# 8_Relay_Buzz_SCT013.net
KiCad netlist of a schematic drawn in EAGLE
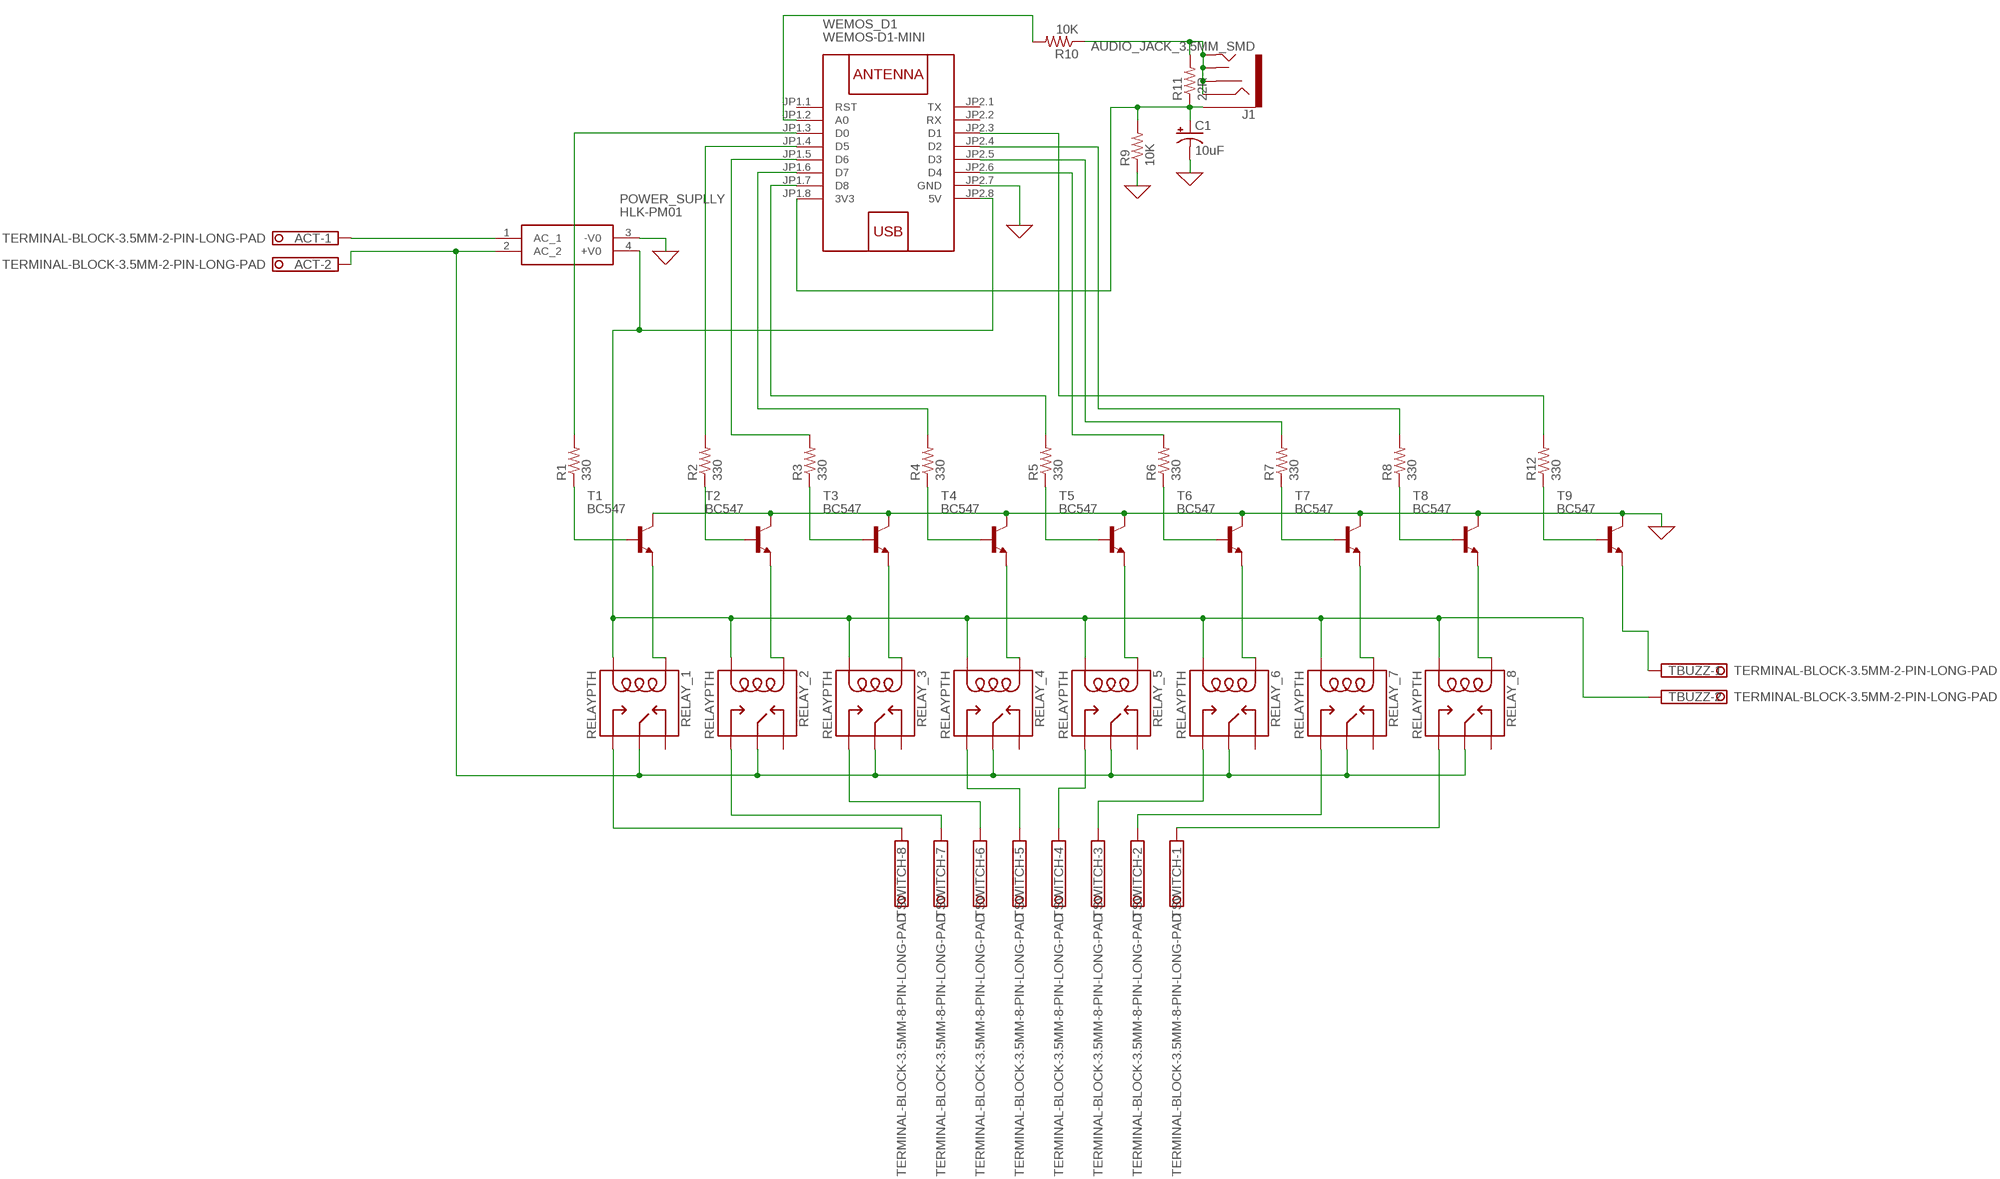
[diagram p0: schematic, sheet 1]

(export (version "E")
  (design (tool "Eeschema 10.0.6"))
  (components
    (comp (ref "ACT")
      (value "TERMINAL-BLOCK-3.5MM-2-PIN-LONG-PAD")
      (footprint "eagle-import:TERMINAL-BLOCK-2-PIN-3.5MM-LONG-PAD")
      (libsource (lib "eagle-import") (part "TERMINAL-BLOCK-3.5MM-2-PIN-LONG-PAD"))
    )
    (comp (ref "C1")
      (value "10uF")
      (footprint "eagle-import:E3,5-8")
      (libsource (lib "eagle-import") (part "CPOL-USE3.5-8"))
    )
    (comp (ref "J1")
      (value "AUDIO_JACK_3.5MM_SMD")
      (footprint "eagle-import:AUDIO-JACK-3.5MM-SMD")
      (libsource (lib "eagle-import") (part "AUDIO_JACK_3.5MM_SMD"))
    )
    (comp (ref "POWER_SUPLLY")
      (value "HLK-PM01")
      (footprint "eagle-import:HLKPM01")
      (fields (field (name "MF") "Hi-link") (field (name "MP") "hlk-pm01"))
      (libsource (lib "eagle-import") (part "HLK-PM01"))
    )
    (comp (ref "R1")
      (value "330")
      (footprint "eagle-import:0207_5V")
      (libsource (lib "eagle-import") (part "R-US_0207/5V"))
    )
    (comp (ref "R2")
      (value "330")
      (footprint "eagle-import:0207_5V")
      (libsource (lib "eagle-import") (part "R-US_0207/5V"))
    )
    (comp (ref "R3")
      (value "330")
      (footprint "eagle-import:0207_5V")
      (libsource (lib "eagle-import") (part "R-US_0207/5V"))
    )
    (comp (ref "R4")
      (value "330")
      (footprint "eagle-import:0207_5V")
      (libsource (lib "eagle-import") (part "R-US_0207/5V"))
    )
    (comp (ref "R5")
      (value "330")
      (footprint "eagle-import:0207_5V")
      (libsource (lib "eagle-import") (part "R-US_0207/5V"))
    )
    (comp (ref "R6")
      (value "330")
      (footprint "eagle-import:0207_5V")
      (libsource (lib "eagle-import") (part "R-US_0207/5V"))
    )
    (comp (ref "R7")
      (value "330")
      (footprint "eagle-import:0207_5V")
      (libsource (lib "eagle-import") (part "R-US_0207/5V"))
    )
    (comp (ref "R8")
      (value "330")
      (footprint "eagle-import:0207_5V")
      (libsource (lib "eagle-import") (part "R-US_0207/5V"))
    )
    (comp (ref "R9")
      (value "10K")
      (footprint "eagle-import:0207_5V")
      (libsource (lib "eagle-import") (part "R-US_0207/5V"))
    )
    (comp (ref "R10")
      (value "10K")
      (footprint "eagle-import:0207_5V")
      (libsource (lib "eagle-import") (part "R-US_0207/5V"))
    )
    (comp (ref "R11")
      (value "22R")
      (footprint "eagle-import:0207_5V")
      (libsource (lib "eagle-import") (part "R-US_0207/5V"))
    )
    (comp (ref "R12")
      (value "330")
      (footprint "eagle-import:0207_5V")
      (libsource (lib "eagle-import") (part "R-US_0207/5V"))
    )
    (comp (ref "RELAY_1")
      (value "RELAYPTH")
      (footprint "eagle-import:SRD-05VDC-SL-C")
      (libsource (lib "eagle-import") (part "RELAYPTH"))
    )
    (comp (ref "RELAY_2")
      (value "RELAYPTH")
      (footprint "eagle-import:SRD-05VDC-SL-C")
      (libsource (lib "eagle-import") (part "RELAYPTH"))
    )
    (comp (ref "RELAY_3")
      (value "RELAYPTH")
      (footprint "eagle-import:SRD-05VDC-SL-C")
      (libsource (lib "eagle-import") (part "RELAYPTH"))
    )
    (comp (ref "RELAY_4")
      (value "RELAYPTH")
      (footprint "eagle-import:SRD-05VDC-SL-C")
      (libsource (lib "eagle-import") (part "RELAYPTH"))
    )
    (comp (ref "RELAY_5")
      (value "RELAYPTH")
      (footprint "eagle-import:SRD-05VDC-SL-C")
      (libsource (lib "eagle-import") (part "RELAYPTH"))
    )
    (comp (ref "RELAY_6")
      (value "RELAYPTH")
      (footprint "eagle-import:SRD-05VDC-SL-C")
      (libsource (lib "eagle-import") (part "RELAYPTH"))
    )
    (comp (ref "RELAY_7")
      (value "RELAYPTH")
      (footprint "eagle-import:SRD-05VDC-SL-C")
      (libsource (lib "eagle-import") (part "RELAYPTH"))
    )
    (comp (ref "RELAY_8")
      (value "RELAYPTH")
      (footprint "eagle-import:SRD-05VDC-SL-C")
      (libsource (lib "eagle-import") (part "RELAYPTH"))
    )
    (comp (ref "T1")
      (value "BC547")
      (footprint "eagle-import:TO92")
      (libsource (lib "eagle-import") (part "BC547"))
    )
    (comp (ref "T2")
      (value "BC547")
      (footprint "eagle-import:TO92")
      (libsource (lib "eagle-import") (part "BC547"))
    )
    (comp (ref "T3")
      (value "BC547")
      (footprint "eagle-import:TO92")
      (libsource (lib "eagle-import") (part "BC547"))
    )
    (comp (ref "T4")
      (value "BC547")
      (footprint "eagle-import:TO92")
      (libsource (lib "eagle-import") (part "BC547"))
    )
    (comp (ref "T5")
      (value "BC547")
      (footprint "eagle-import:TO92")
      (libsource (lib "eagle-import") (part "BC547"))
    )
    (comp (ref "T6")
      (value "BC547")
      (footprint "eagle-import:TO92")
      (libsource (lib "eagle-import") (part "BC547"))
    )
    (comp (ref "T7")
      (value "BC547")
      (footprint "eagle-import:TO92")
      (libsource (lib "eagle-import") (part "BC547"))
    )
    (comp (ref "T8")
      (value "BC547")
      (footprint "eagle-import:TO92")
      (libsource (lib "eagle-import") (part "BC547"))
    )
    (comp (ref "T9")
      (value "BC547")
      (footprint "eagle-import:TO92")
      (libsource (lib "eagle-import") (part "BC547"))
    )
    (comp (ref "TBUZZ")
      (value "TERMINAL-BLOCK-3.5MM-2-PIN-LONG-PAD")
      (footprint "eagle-import:TERMINAL-BLOCK-2-PIN-3.5MM-LONG-PAD")
      (libsource (lib "eagle-import") (part "TERMINAL-BLOCK-3.5MM-2-PIN-LONG-PAD"))
    )
    (comp (ref "TSWITCH")
      (value "TERMINAL-BLOCK-3.5MM-8-PIN-LONG-PAD")
      (footprint "eagle-import:TERMINAL-BLOCK-8-PIN-3.5MM-LONG-PAD")
      (libsource (lib "eagle-import") (part "TERMINAL-BLOCK-3.5MM-8-PIN-LONG-PAD"))
    )
    (comp (ref "WEMOS_D1")
      (value "WEMOS-D1-MINI")
      (footprint "eagle-import:WEMOS-D1-MINI")
      (libsource (lib "eagle-import") (part "WEMOS-D1-MINI"))
    )
  )
  (nets
    (net (code "1") (name "GND") (class "Default")
      (node (ref "C1") (pin "-") (pinfunction "-_-") (pintype "passive"))
      (node (ref "POWER_SUPLLY") (pin "3") (pinfunction "-V0_3") (pintype "bidirectional"))
      (node (ref "R9") (pin "1") (pinfunction "1_1") (pintype "passive"))
      (node (ref "T1") (pin "3") (pinfunction "C_3") (pintype "passive"))
      (node (ref "T2") (pin "3") (pinfunction "C_3") (pintype "passive"))
      (node (ref "T3") (pin "3") (pinfunction "C_3") (pintype "passive"))
      (node (ref "T4") (pin "3") (pinfunction "C_3") (pintype "passive"))
      (node (ref "T5") (pin "3") (pinfunction "C_3") (pintype "passive"))
      (node (ref "T6") (pin "3") (pinfunction "C_3") (pintype "passive"))
      (node (ref "T7") (pin "3") (pinfunction "C_3") (pintype "passive"))
      (node (ref "T8") (pin "3") (pinfunction "C_3") (pintype "passive"))
      (node (ref "T9") (pin "3") (pinfunction "C_3") (pintype "passive"))
      (node (ref "WEMOS_D1") (pin "JP2.7") (pinfunction "GND_JP2.7") (pintype "power_in"))
    )
    (net (code "2") (name "Net-(ACTA-K)") (class "Default")
      (node (ref "ACT") (pin "1") (pinfunction "K_1") (pintype "passive"))
      (node (ref "POWER_SUPLLY") (pin "1") (pinfunction "AC_1_1") (pintype "bidirectional"))
    )
    (net (code "3") (name "Net-(ACTB-K)") (class "Default")
      (node (ref "ACT") (pin "2") (pinfunction "K_2") (pintype "passive"))
      (node (ref "POWER_SUPLLY") (pin "2") (pinfunction "AC_2_2") (pintype "bidirectional"))
      (node (ref "RELAY_1") (pin "SWCOMMON") (pinfunction "SWCOMMON_SWCOMMON") (pintype "bidirectional"))
      (node (ref "RELAY_2") (pin "SWCOMMON") (pinfunction "SWCOMMON_SWCOMMON") (pintype "bidirectional"))
      (node (ref "RELAY_3") (pin "SWCOMMON") (pinfunction "SWCOMMON_SWCOMMON") (pintype "bidirectional"))
      (node (ref "RELAY_4") (pin "SWCOMMON") (pinfunction "SWCOMMON_SWCOMMON") (pintype "bidirectional"))
      (node (ref "RELAY_5") (pin "SWCOMMON") (pinfunction "SWCOMMON_SWCOMMON") (pintype "bidirectional"))
      (node (ref "RELAY_6") (pin "SWCOMMON") (pinfunction "SWCOMMON_SWCOMMON") (pintype "bidirectional"))
      (node (ref "RELAY_7") (pin "SWCOMMON") (pinfunction "SWCOMMON_SWCOMMON") (pintype "bidirectional"))
      (node (ref "RELAY_8") (pin "SWCOMMON") (pinfunction "SWCOMMON_SWCOMMON") (pintype "bidirectional"))
    )
    (net (code "4") (name "Net-(J1-PadRING)") (class "Default")
      (node (ref "J1") (pin "RING") (pinfunction "RING_RING") (pintype "bidirectional"))
      (node (ref "J1") (pin "RSH") (pinfunction "RSH_RSH") (pintype "bidirectional"))
      (node (ref "J1") (pin "TIP") (pinfunction "TIP_TIP") (pintype "bidirectional"))
      (node (ref "J1") (pin "TSH") (pinfunction "TSH_TSH") (pintype "bidirectional"))
      (node (ref "R10") (pin "1") (pinfunction "1_1") (pintype "passive"))
      (node (ref "R11") (pin "2") (pinfunction "2_2") (pintype "passive"))
    )
    (net (code "5") (name "Net-(POWER_SUPLLY-+V0)") (class "Default")
      (node (ref "POWER_SUPLLY") (pin "4") (pinfunction "+V0_4") (pintype "bidirectional"))
      (node (ref "RELAY_1") (pin "COIL0") (pinfunction "COIL0_COIL0") (pintype "bidirectional"))
      (node (ref "RELAY_2") (pin "COIL0") (pinfunction "COIL0_COIL0") (pintype "bidirectional"))
      (node (ref "RELAY_3") (pin "COIL0") (pinfunction "COIL0_COIL0") (pintype "bidirectional"))
      (node (ref "RELAY_4") (pin "COIL0") (pinfunction "COIL0_COIL0") (pintype "bidirectional"))
      (node (ref "RELAY_5") (pin "COIL0") (pinfunction "COIL0_COIL0") (pintype "bidirectional"))
      (node (ref "RELAY_6") (pin "COIL0") (pinfunction "COIL0_COIL0") (pintype "bidirectional"))
      (node (ref "RELAY_7") (pin "COIL0") (pinfunction "COIL0_COIL0") (pintype "bidirectional"))
      (node (ref "RELAY_8") (pin "COIL0") (pinfunction "COIL0_COIL0") (pintype "bidirectional"))
      (node (ref "TBUZZ") (pin "2") (pinfunction "K_2") (pintype "passive"))
      (node (ref "WEMOS_D1") (pin "JP2.8") (pinfunction "5V_JP2.8") (pintype "power_in"))
    )
    (net (code "6") (name "Net-(T1-B)") (class "Default")
      (node (ref "R1") (pin "1") (pinfunction "1_1") (pintype "passive"))
      (node (ref "T1") (pin "2") (pinfunction "B_2") (pintype "passive"))
    )
    (net (code "7") (name "Net-(T1-E)") (class "Default")
      (node (ref "RELAY_1") (pin "COIL1") (pinfunction "COIL1_COIL1") (pintype "bidirectional"))
      (node (ref "T1") (pin "1") (pinfunction "E_1") (pintype "passive"))
    )
    (net (code "8") (name "Net-(T2-B)") (class "Default")
      (node (ref "R2") (pin "1") (pinfunction "1_1") (pintype "passive"))
      (node (ref "T2") (pin "2") (pinfunction "B_2") (pintype "passive"))
    )
    (net (code "9") (name "Net-(T2-E)") (class "Default")
      (node (ref "RELAY_2") (pin "COIL1") (pinfunction "COIL1_COIL1") (pintype "bidirectional"))
      (node (ref "T2") (pin "1") (pinfunction "E_1") (pintype "passive"))
    )
    (net (code "10") (name "Net-(T3-B)") (class "Default")
      (node (ref "R3") (pin "1") (pinfunction "1_1") (pintype "passive"))
      (node (ref "T3") (pin "2") (pinfunction "B_2") (pintype "passive"))
    )
    (net (code "11") (name "Net-(T3-E)") (class "Default")
      (node (ref "RELAY_3") (pin "COIL1") (pinfunction "COIL1_COIL1") (pintype "bidirectional"))
      (node (ref "T3") (pin "1") (pinfunction "E_1") (pintype "passive"))
    )
    (net (code "12") (name "Net-(T4-B)") (class "Default")
      (node (ref "R4") (pin "1") (pinfunction "1_1") (pintype "passive"))
      (node (ref "T4") (pin "2") (pinfunction "B_2") (pintype "passive"))
    )
    (net (code "13") (name "Net-(T4-E)") (class "Default")
      (node (ref "RELAY_4") (pin "COIL1") (pinfunction "COIL1_COIL1") (pintype "bidirectional"))
      (node (ref "T4") (pin "1") (pinfunction "E_1") (pintype "passive"))
    )
    (net (code "14") (name "Net-(T5-B)") (class "Default")
      (node (ref "R5") (pin "1") (pinfunction "1_1") (pintype "passive"))
      (node (ref "T5") (pin "2") (pinfunction "B_2") (pintype "passive"))
    )
    (net (code "15") (name "Net-(T5-E)") (class "Default")
      (node (ref "RELAY_5") (pin "COIL1") (pinfunction "COIL1_COIL1") (pintype "bidirectional"))
      (node (ref "T5") (pin "1") (pinfunction "E_1") (pintype "passive"))
    )
    (net (code "16") (name "Net-(T6-B)") (class "Default")
      (node (ref "R6") (pin "1") (pinfunction "1_1") (pintype "passive"))
      (node (ref "T6") (pin "2") (pinfunction "B_2") (pintype "passive"))
    )
    (net (code "17") (name "Net-(T6-E)") (class "Default")
      (node (ref "RELAY_6") (pin "COIL1") (pinfunction "COIL1_COIL1") (pintype "bidirectional"))
      (node (ref "T6") (pin "1") (pinfunction "E_1") (pintype "passive"))
    )
    (net (code "18") (name "Net-(T7-B)") (class "Default")
      (node (ref "R7") (pin "1") (pinfunction "1_1") (pintype "passive"))
      (node (ref "T7") (pin "2") (pinfunction "B_2") (pintype "passive"))
    )
    (net (code "19") (name "Net-(T7-E)") (class "Default")
      (node (ref "RELAY_7") (pin "COIL1") (pinfunction "COIL1_COIL1") (pintype "bidirectional"))
      (node (ref "T7") (pin "1") (pinfunction "E_1") (pintype "passive"))
    )
    (net (code "20") (name "Net-(T8-B)") (class "Default")
      (node (ref "R8") (pin "1") (pinfunction "1_1") (pintype "passive"))
      (node (ref "T8") (pin "2") (pinfunction "B_2") (pintype "passive"))
    )
    (net (code "21") (name "Net-(T8-E)") (class "Default")
      (node (ref "RELAY_8") (pin "COIL1") (pinfunction "COIL1_COIL1") (pintype "bidirectional"))
      (node (ref "T8") (pin "1") (pinfunction "E_1") (pintype "passive"))
    )
    (net (code "22") (name "Net-(T9-B)") (class "Default")
      (node (ref "R12") (pin "1") (pinfunction "1_1") (pintype "passive"))
      (node (ref "T9") (pin "2") (pinfunction "B_2") (pintype "passive"))
    )
    (net (code "23") (name "Net-(T9-E)") (class "Default")
      (node (ref "T9") (pin "1") (pinfunction "E_1") (pintype "passive"))
      (node (ref "TBUZZ") (pin "1") (pinfunction "K_1") (pintype "passive"))
    )
    (net (code "24") (name "Net-(TSWITCHA-K)") (class "Default")
      (node (ref "RELAY_8") (pin "SWOPEN") (pinfunction "SWOPEN_SWOPEN") (pintype "bidirectional"))
      (node (ref "TSWITCH") (pin "1") (pinfunction "K_1") (pintype "passive"))
    )
    (net (code "25") (name "Net-(TSWITCHB-K)") (class "Default")
      (node (ref "RELAY_7") (pin "SWOPEN") (pinfunction "SWOPEN_SWOPEN") (pintype "bidirectional"))
      (node (ref "TSWITCH") (pin "2") (pinfunction "K_2") (pintype "passive"))
    )
    (net (code "26") (name "Net-(TSWITCHC-K)") (class "Default")
      (node (ref "RELAY_6") (pin "SWOPEN") (pinfunction "SWOPEN_SWOPEN") (pintype "bidirectional"))
      (node (ref "TSWITCH") (pin "3") (pinfunction "K_3") (pintype "passive"))
    )
    (net (code "27") (name "Net-(TSWITCHD-K)") (class "Default")
      (node (ref "RELAY_5") (pin "SWOPEN") (pinfunction "SWOPEN_SWOPEN") (pintype "bidirectional"))
      (node (ref "TSWITCH") (pin "4") (pinfunction "K_4") (pintype "passive"))
    )
    (net (code "28") (name "Net-(TSWITCHE-K)") (class "Default")
      (node (ref "RELAY_4") (pin "SWOPEN") (pinfunction "SWOPEN_SWOPEN") (pintype "bidirectional"))
      (node (ref "TSWITCH") (pin "5") (pinfunction "K_5") (pintype "passive"))
    )
    (net (code "29") (name "Net-(TSWITCHF-K)") (class "Default")
      (node (ref "RELAY_3") (pin "SWOPEN") (pinfunction "SWOPEN_SWOPEN") (pintype "bidirectional"))
      (node (ref "TSWITCH") (pin "6") (pinfunction "K_6") (pintype "passive"))
    )
    (net (code "30") (name "Net-(TSWITCHG-K)") (class "Default")
      (node (ref "RELAY_2") (pin "SWOPEN") (pinfunction "SWOPEN_SWOPEN") (pintype "bidirectional"))
      (node (ref "TSWITCH") (pin "7") (pinfunction "K_7") (pintype "passive"))
    )
    (net (code "31") (name "Net-(TSWITCHH-K)") (class "Default")
      (node (ref "RELAY_1") (pin "SWOPEN") (pinfunction "SWOPEN_SWOPEN") (pintype "bidirectional"))
      (node (ref "TSWITCH") (pin "8") (pinfunction "K_8") (pintype "passive"))
    )
    (net (code "32") (name "Net-(WEMOS_D1-3V3)") (class "Default")
      (node (ref "C1") (pin "+") (pinfunction "+_+") (pintype "passive"))
      (node (ref "J1") (pin "SLEEVE") (pinfunction "SLEEVE_SLEEVE") (pintype "bidirectional"))
      (node (ref "R11") (pin "1") (pinfunction "1_1") (pintype "passive"))
      (node (ref "R9") (pin "2") (pinfunction "2_2") (pintype "passive"))
      (node (ref "WEMOS_D1") (pin "JP1.8") (pinfunction "3V3_JP1.8") (pintype "power_in"))
    )
    (net (code "33") (name "Net-(WEMOS_D1-A0)") (class "Default")
      (node (ref "R10") (pin "2") (pinfunction "2_2") (pintype "passive"))
      (node (ref "WEMOS_D1") (pin "JP1.2") (pinfunction "A0_JP1.2") (pintype "bidirectional"))
    )
    (net (code "34") (name "Net-(WEMOS_D1-D0)") (class "Default")
      (node (ref "R1") (pin "2") (pinfunction "2_2") (pintype "passive"))
      (node (ref "WEMOS_D1") (pin "JP1.3") (pinfunction "D0_JP1.3") (pintype "bidirectional"))
    )
    (net (code "35") (name "Net-(WEMOS_D1-D1)") (class "Default")
      (node (ref "R12") (pin "2") (pinfunction "2_2") (pintype "passive"))
      (node (ref "WEMOS_D1") (pin "JP2.3") (pinfunction "D1_JP2.3") (pintype "bidirectional"))
    )
    (net (code "36") (name "Net-(WEMOS_D1-D2)") (class "Default")
      (node (ref "R8") (pin "2") (pinfunction "2_2") (pintype "passive"))
      (node (ref "WEMOS_D1") (pin "JP2.4") (pinfunction "D2_JP2.4") (pintype "bidirectional"))
    )
    (net (code "37") (name "Net-(WEMOS_D1-D3)") (class "Default")
      (node (ref "R7") (pin "2") (pinfunction "2_2") (pintype "passive"))
      (node (ref "WEMOS_D1") (pin "JP2.5") (pinfunction "D3_JP2.5") (pintype "bidirectional"))
    )
    (net (code "38") (name "Net-(WEMOS_D1-D4)") (class "Default")
      (node (ref "R6") (pin "2") (pinfunction "2_2") (pintype "passive"))
      (node (ref "WEMOS_D1") (pin "JP2.6") (pinfunction "D4_JP2.6") (pintype "bidirectional"))
    )
    (net (code "39") (name "Net-(WEMOS_D1-D5)") (class "Default")
      (node (ref "R2") (pin "2") (pinfunction "2_2") (pintype "passive"))
      (node (ref "WEMOS_D1") (pin "JP1.4") (pinfunction "D5_JP1.4") (pintype "bidirectional"))
    )
    (net (code "40") (name "Net-(WEMOS_D1-D6)") (class "Default")
      (node (ref "R3") (pin "2") (pinfunction "2_2") (pintype "passive"))
      (node (ref "WEMOS_D1") (pin "JP1.5") (pinfunction "D6_JP1.5") (pintype "bidirectional"))
    )
    (net (code "41") (name "Net-(WEMOS_D1-D7)") (class "Default")
      (node (ref "R4") (pin "2") (pinfunction "2_2") (pintype "passive"))
      (node (ref "WEMOS_D1") (pin "JP1.6") (pinfunction "D7_JP1.6") (pintype "bidirectional"))
    )
    (net (code "42") (name "Net-(WEMOS_D1-D8)") (class "Default")
      (node (ref "R5") (pin "2") (pinfunction "2_2") (pintype "passive"))
      (node (ref "WEMOS_D1") (pin "JP1.7") (pinfunction "D8_JP1.7") (pintype "bidirectional"))
    )
    (net (code "43") (name "unconnected-(RELAY_1-SWCLOSE-PadSWCLOSED)") (class "Default")
      (node (ref "RELAY_1") (pin "SWCLOSED") (pinfunction "SWCLOSE_SWCLOSED") (pintype "bidirectional"))
    )
    (net (code "44") (name "unconnected-(RELAY_2-SWCLOSE-PadSWCLOSED)") (class "Default")
      (node (ref "RELAY_2") (pin "SWCLOSED") (pinfunction "SWCLOSE_SWCLOSED") (pintype "bidirectional"))
    )
    (net (code "45") (name "unconnected-(RELAY_3-SWCLOSE-PadSWCLOSED)") (class "Default")
      (node (ref "RELAY_3") (pin "SWCLOSED") (pinfunction "SWCLOSE_SWCLOSED") (pintype "bidirectional"))
    )
    (net (code "46") (name "unconnected-(RELAY_4-SWCLOSE-PadSWCLOSED)") (class "Default")
      (node (ref "RELAY_4") (pin "SWCLOSED") (pinfunction "SWCLOSE_SWCLOSED") (pintype "bidirectional"))
    )
    (net (code "47") (name "unconnected-(RELAY_5-SWCLOSE-PadSWCLOSED)") (class "Default")
      (node (ref "RELAY_5") (pin "SWCLOSED") (pinfunction "SWCLOSE_SWCLOSED") (pintype "bidirectional"))
    )
    (net (code "48") (name "unconnected-(RELAY_6-SWCLOSE-PadSWCLOSED)") (class "Default")
      (node (ref "RELAY_6") (pin "SWCLOSED") (pinfunction "SWCLOSE_SWCLOSED") (pintype "bidirectional"))
    )
    (net (code "49") (name "unconnected-(RELAY_7-SWCLOSE-PadSWCLOSED)") (class "Default")
      (node (ref "RELAY_7") (pin "SWCLOSED") (pinfunction "SWCLOSE_SWCLOSED") (pintype "bidirectional"))
    )
    (net (code "50") (name "unconnected-(RELAY_8-SWCLOSE-PadSWCLOSED)") (class "Default")
      (node (ref "RELAY_8") (pin "SWCLOSED") (pinfunction "SWCLOSE_SWCLOSED") (pintype "bidirectional"))
    )
    (net (code "51") (name "unconnected-(WEMOS_D1-RST-PadJP1.1)") (class "Default")
      (node (ref "WEMOS_D1") (pin "JP1.1") (pinfunction "RST_JP1.1") (pintype "bidirectional"))
    )
    (net (code "52") (name "unconnected-(WEMOS_D1-RX-PadJP2.2)") (class "Default")
      (node (ref "WEMOS_D1") (pin "JP2.2") (pinfunction "RX_JP2.2") (pintype "bidirectional"))
    )
    (net (code "53") (name "unconnected-(WEMOS_D1-TX-PadJP2.1)") (class "Default")
      (node (ref "WEMOS_D1") (pin "JP2.1") (pinfunction "TX_JP2.1") (pintype "bidirectional"))
    )
  )
)
